# DRIVER.net
KiCad netlist of a schematic drawn in EAGLE
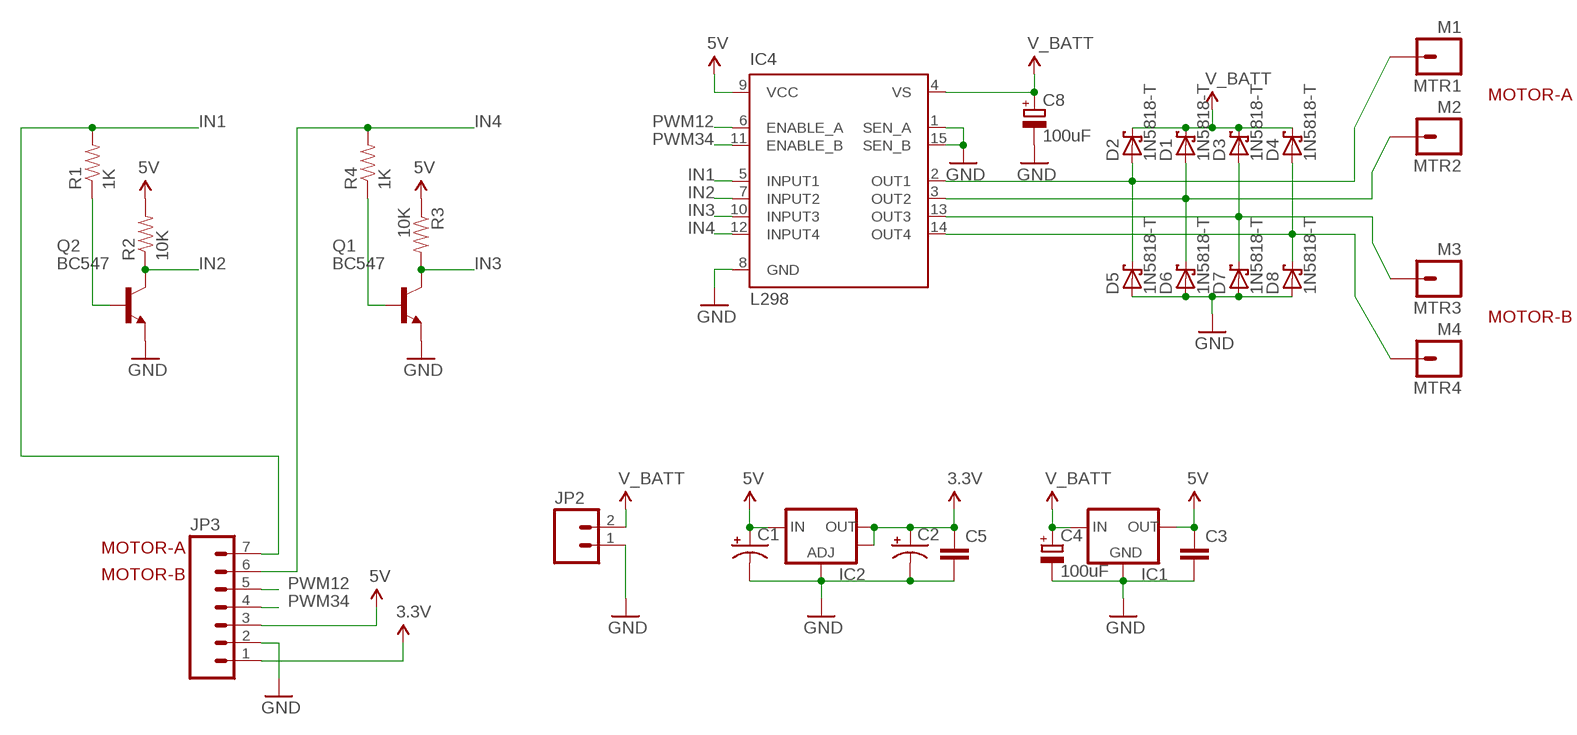
[diagram p0: schematic, sheet 1]

(export (version "E")
  (design (tool "Eeschema 10.0.6"))
  (components
    (comp (ref "C1")
      (value "CAP_POL1206-KIT")
      (footprint "eagle-import:EIA3216-KIT")
      (libsource (lib "eagle-import") (part "CAP_POL1206-KIT"))
    )
    (comp (ref "C2")
      (value "CAP_POL1206-KIT")
      (footprint "eagle-import:EIA3216-KIT")
      (libsource (lib "eagle-import") (part "CAP_POL1206-KIT"))
    )
    (comp (ref "C3")
      (value "CAPPTH")
      (footprint "eagle-import:CAP-PTH-SMALL")
      (libsource (lib "eagle-import") (part "CAPPTH"))
    )
    (comp (ref "C4")
      (value "100uF")
      (footprint "eagle-import:E2,5-5")
      (libsource (lib "eagle-import") (part "CPOL-EUE2.5-5"))
    )
    (comp (ref "C5")
      (value "CAP0805")
      (footprint "eagle-import:0805")
      (libsource (lib "eagle-import") (part "CAP0805"))
    )
    (comp (ref "C8")
      (value "100uF")
      (footprint "eagle-import:E2,5-5")
      (libsource (lib "eagle-import") (part "CPOL-EUE2.5-5"))
    )
    (comp (ref "D1")
      (value "1N5818-T")
      (footprint "eagle-import:DO41-7.6")
      (libsource (lib "eagle-import") (part "1N5818-T"))
    )
    (comp (ref "D2")
      (value "1N5818-T")
      (footprint "eagle-import:DO41-7.6")
      (libsource (lib "eagle-import") (part "1N5818-T"))
    )
    (comp (ref "D3")
      (value "1N5818-T")
      (footprint "eagle-import:DO41-7.6")
      (libsource (lib "eagle-import") (part "1N5818-T"))
    )
    (comp (ref "D4")
      (value "1N5818-T")
      (footprint "eagle-import:DO41-7.6")
      (libsource (lib "eagle-import") (part "1N5818-T"))
    )
    (comp (ref "D5")
      (value "1N5818-T")
      (footprint "eagle-import:DO41-7.6")
      (libsource (lib "eagle-import") (part "1N5818-T"))
    )
    (comp (ref "D6")
      (value "1N5818-T")
      (footprint "eagle-import:DO41-7.6")
      (libsource (lib "eagle-import") (part "1N5818-T"))
    )
    (comp (ref "D7")
      (value "1N5818-T")
      (footprint "eagle-import:DO41-7.6")
      (libsource (lib "eagle-import") (part "1N5818-T"))
    )
    (comp (ref "D8")
      (value "1N5818-T")
      (footprint "eagle-import:DO41-7.6")
      (libsource (lib "eagle-import") (part "1N5818-T"))
    )
    (comp (ref "IC1")
      (value "V_REG_78XX-TO-220")
      (footprint "eagle-import:TO-220-ALT")
      (libsource (lib "eagle-import") (part "V_REG_78XX-TO-220"))
    )
    (comp (ref "IC2")
      (value "V_REG_LM1117SOT223")
      (footprint "eagle-import:SOT223")
      (libsource (lib "eagle-import") (part "V_REG_LM1117SOT223"))
    )
    (comp (ref "IC4")
      (value "L298")
      (footprint "eagle-import:MULTIWATT-15")
      (fields (field (name "MPN") "L298N"))
      (libsource (lib "eagle-import") (part "L298"))
    )
    (comp (ref "JP2")
      (value "M02LOCK_LONGPADS")
      (footprint "eagle-import:1X02_LOCK_LONGPADS")
      (libsource (lib "eagle-import") (part "M02LOCK_LONGPADS"))
    )
    (comp (ref "JP3")
      (value "M07LONGPADS")
      (footprint "eagle-import:1X07_LONGPADS")
      (libsource (lib "eagle-import") (part "M07LONGPADS"))
    )
    (comp (ref "MTR1")
      (value "M1")
      (footprint "eagle-import:1X01_LONGPAD")
      (libsource (lib "eagle-import") (part "M01PTH_LONGPAD"))
    )
    (comp (ref "MTR2")
      (value "M2")
      (footprint "eagle-import:1X01_LONGPAD")
      (libsource (lib "eagle-import") (part "M01PTH_LONGPAD"))
    )
    (comp (ref "MTR3")
      (value "M3")
      (footprint "eagle-import:1X01_LONGPAD")
      (libsource (lib "eagle-import") (part "M01PTH_LONGPAD"))
    )
    (comp (ref "MTR4")
      (value "M4")
      (footprint "eagle-import:1X01_LONGPAD")
      (libsource (lib "eagle-import") (part "M01PTH_LONGPAD"))
    )
    (comp (ref "Q1")
      (value "BC547")
      (footprint "eagle-import:TO92")
      (libsource (lib "eagle-import") (part "BC547"))
    )
    (comp (ref "Q2")
      (value "BC547")
      (footprint "eagle-import:TO92")
      (libsource (lib "eagle-import") (part "BC547"))
    )
    (comp (ref "R1")
      (value "1K")
      (footprint "eagle-import:0805")
      (libsource (lib "eagle-import") (part "RESISTOR0805-RES"))
    )
    (comp (ref "R2")
      (value "10K")
      (footprint "eagle-import:0805")
      (libsource (lib "eagle-import") (part "RESISTOR0805-RES"))
    )
    (comp (ref "R3")
      (value "10K")
      (footprint "eagle-import:0805")
      (libsource (lib "eagle-import") (part "RESISTOR0805-RES"))
    )
    (comp (ref "R4")
      (value "1K")
      (footprint "eagle-import:0805")
      (libsource (lib "eagle-import") (part "RESISTOR0805-RES"))
    )
  )
  (nets
    (net (code "1") (name "/IN1") (class "Default")
      (node (ref "IC4") (pin "5") (pinfunction "INPUT1_5") (pintype "input"))
      (node (ref "JP3") (pin "7") (pinfunction "7_7") (pintype "passive"))
      (node (ref "R1") (pin "2") (pinfunction "2_2") (pintype "passive"))
    )
    (net (code "2") (name "/IN2") (class "Default")
      (node (ref "IC4") (pin "7") (pinfunction "INPUT2_7") (pintype "input"))
      (node (ref "Q2") (pin "3") (pinfunction "C_3") (pintype "passive"))
      (node (ref "R2") (pin "1") (pinfunction "1_1") (pintype "passive"))
    )
    (net (code "3") (name "/IN3") (class "Default")
      (node (ref "IC4") (pin "10") (pinfunction "INPUT3_10") (pintype "input"))
      (node (ref "Q1") (pin "3") (pinfunction "C_3") (pintype "passive"))
      (node (ref "R3") (pin "2") (pinfunction "2_2") (pintype "passive"))
    )
    (net (code "4") (name "/IN4") (class "Default")
      (node (ref "IC4") (pin "12") (pinfunction "INPUT4_12") (pintype "input"))
      (node (ref "JP3") (pin "6") (pinfunction "6_6") (pintype "passive"))
      (node (ref "R4") (pin "2") (pinfunction "2_2") (pintype "passive"))
    )
    (net (code "5") (name "/PWM12") (class "Default")
      (node (ref "IC4") (pin "6") (pinfunction "ENABLE_A_6") (pintype "input"))
      (node (ref "JP3") (pin "5") (pinfunction "5_5") (pintype "passive"))
    )
    (net (code "6") (name "/PWM34") (class "Default")
      (node (ref "IC4") (pin "11") (pinfunction "ENABLE_B_11") (pintype "input"))
      (node (ref "JP3") (pin "4") (pinfunction "4_4") (pintype "passive"))
    )
    (net (code "7") (name "3.3V") (class "Default")
      (node (ref "C2") (pin "A") (pinfunction "+_A") (pintype "passive"))
      (node (ref "C5") (pin "1") (pinfunction "1_1") (pintype "passive"))
      (node (ref "IC2") (pin "2") (pinfunction "OUT_2") (pintype "output"))
      (node (ref "IC2") (pin "4") (pinfunction "OUT_4") (pintype "output"))
      (node (ref "JP3") (pin "1") (pinfunction "1_1") (pintype "passive"))
    )
    (net (code "8") (name "5V") (class "Default")
      (node (ref "C1") (pin "A") (pinfunction "+_A") (pintype "passive"))
      (node (ref "C3") (pin "1") (pinfunction "1_1") (pintype "passive"))
      (node (ref "IC1") (pin "OUT") (pinfunction "OUT_OUT") (pintype "output"))
      (node (ref "IC2") (pin "3") (pinfunction "IN_3") (pintype "input"))
      (node (ref "IC4") (pin "9") (pinfunction "VCC_9") (pintype "power_in"))
      (node (ref "JP3") (pin "3") (pinfunction "3_3") (pintype "passive"))
      (node (ref "R2") (pin "2") (pinfunction "2_2") (pintype "passive"))
      (node (ref "R3") (pin "1") (pinfunction "1_1") (pintype "passive"))
    )
    (net (code "9") (name "GND") (class "Default")
      (node (ref "C1") (pin "C") (pinfunction "-_C") (pintype "passive"))
      (node (ref "C2") (pin "C") (pinfunction "-_C") (pintype "passive"))
      (node (ref "C3") (pin "2") (pinfunction "2_2") (pintype "passive"))
      (node (ref "C4") (pin "-") (pinfunction "-_-") (pintype "passive"))
      (node (ref "C5") (pin "2") (pinfunction "2_2") (pintype "passive"))
      (node (ref "C8") (pin "-") (pinfunction "-_-") (pintype "passive"))
      (node (ref "D5") (pin "A") (pinfunction "A_A") (pintype "passive"))
      (node (ref "D6") (pin "A") (pinfunction "A_A") (pintype "passive"))
      (node (ref "D7") (pin "A") (pinfunction "A_A") (pintype "passive"))
      (node (ref "D8") (pin "A") (pinfunction "A_A") (pintype "passive"))
      (node (ref "IC1") (pin "GND") (pinfunction "GND_GND") (pintype "input"))
      (node (ref "IC2") (pin "1") (pinfunction "ADJ_1") (pintype "input"))
      (node (ref "IC4") (pin "1") (pinfunction "SEN_A_1") (pintype "input"))
      (node (ref "IC4") (pin "15") (pinfunction "SEN_B_15") (pintype "input"))
      (node (ref "IC4") (pin "8") (pinfunction "GND_8") (pintype "power_in"))
      (node (ref "JP2") (pin "1") (pinfunction "1_1") (pintype "passive"))
      (node (ref "JP3") (pin "2") (pinfunction "2_2") (pintype "passive"))
      (node (ref "Q1") (pin "1") (pinfunction "E_1") (pintype "passive"))
      (node (ref "Q2") (pin "1") (pinfunction "E_1") (pintype "passive"))
    )
    (net (code "10") (name "Net-(IC4-OUT1)") (class "Default")
      (node (ref "D2") (pin "A") (pinfunction "A_A") (pintype "passive"))
      (node (ref "D5") (pin "C") (pinfunction "C_C") (pintype "passive"))
      (node (ref "IC4") (pin "2") (pinfunction "OUT1_2") (pintype "output"))
      (node (ref "MTR1") (pin "1") (pinfunction "1_1") (pintype "passive"))
    )
    (net (code "11") (name "Net-(IC4-OUT2)") (class "Default")
      (node (ref "D1") (pin "A") (pinfunction "A_A") (pintype "passive"))
      (node (ref "D6") (pin "C") (pinfunction "C_C") (pintype "passive"))
      (node (ref "IC4") (pin "3") (pinfunction "OUT2_3") (pintype "output"))
      (node (ref "MTR2") (pin "1") (pinfunction "1_1") (pintype "passive"))
    )
    (net (code "12") (name "Net-(IC4-OUT3)") (class "Default")
      (node (ref "D3") (pin "A") (pinfunction "A_A") (pintype "passive"))
      (node (ref "D7") (pin "C") (pinfunction "C_C") (pintype "passive"))
      (node (ref "IC4") (pin "13") (pinfunction "OUT3_13") (pintype "output"))
      (node (ref "MTR3") (pin "1") (pinfunction "1_1") (pintype "passive"))
    )
    (net (code "13") (name "Net-(IC4-OUT4)") (class "Default")
      (node (ref "D4") (pin "A") (pinfunction "A_A") (pintype "passive"))
      (node (ref "D8") (pin "C") (pinfunction "C_C") (pintype "passive"))
      (node (ref "IC4") (pin "14") (pinfunction "OUT4_14") (pintype "output"))
      (node (ref "MTR4") (pin "1") (pinfunction "1_1") (pintype "passive"))
    )
    (net (code "14") (name "Net-(Q1-B)") (class "Default")
      (node (ref "Q1") (pin "2") (pinfunction "B_2") (pintype "passive"))
      (node (ref "R4") (pin "1") (pinfunction "1_1") (pintype "passive"))
    )
    (net (code "15") (name "Net-(Q2-B)") (class "Default")
      (node (ref "Q2") (pin "2") (pinfunction "B_2") (pintype "passive"))
      (node (ref "R1") (pin "1") (pinfunction "1_1") (pintype "passive"))
    )
    (net (code "16") (name "V_BATT") (class "Default")
      (node (ref "C4") (pin "+") (pinfunction "+_+") (pintype "passive"))
      (node (ref "C8") (pin "+") (pinfunction "+_+") (pintype "passive"))
      (node (ref "D1") (pin "C") (pinfunction "C_C") (pintype "passive"))
      (node (ref "D2") (pin "C") (pinfunction "C_C") (pintype "passive"))
      (node (ref "D3") (pin "C") (pinfunction "C_C") (pintype "passive"))
      (node (ref "D4") (pin "C") (pinfunction "C_C") (pintype "passive"))
      (node (ref "IC1") (pin "IN") (pinfunction "IN_IN") (pintype "input"))
      (node (ref "IC4") (pin "4") (pinfunction "VS_4") (pintype "power_in"))
      (node (ref "JP2") (pin "2") (pinfunction "2_2") (pintype "passive"))
    )
  )
)
